# brmbora8.net
KiCad netlist of a schematic drawn in EAGLE
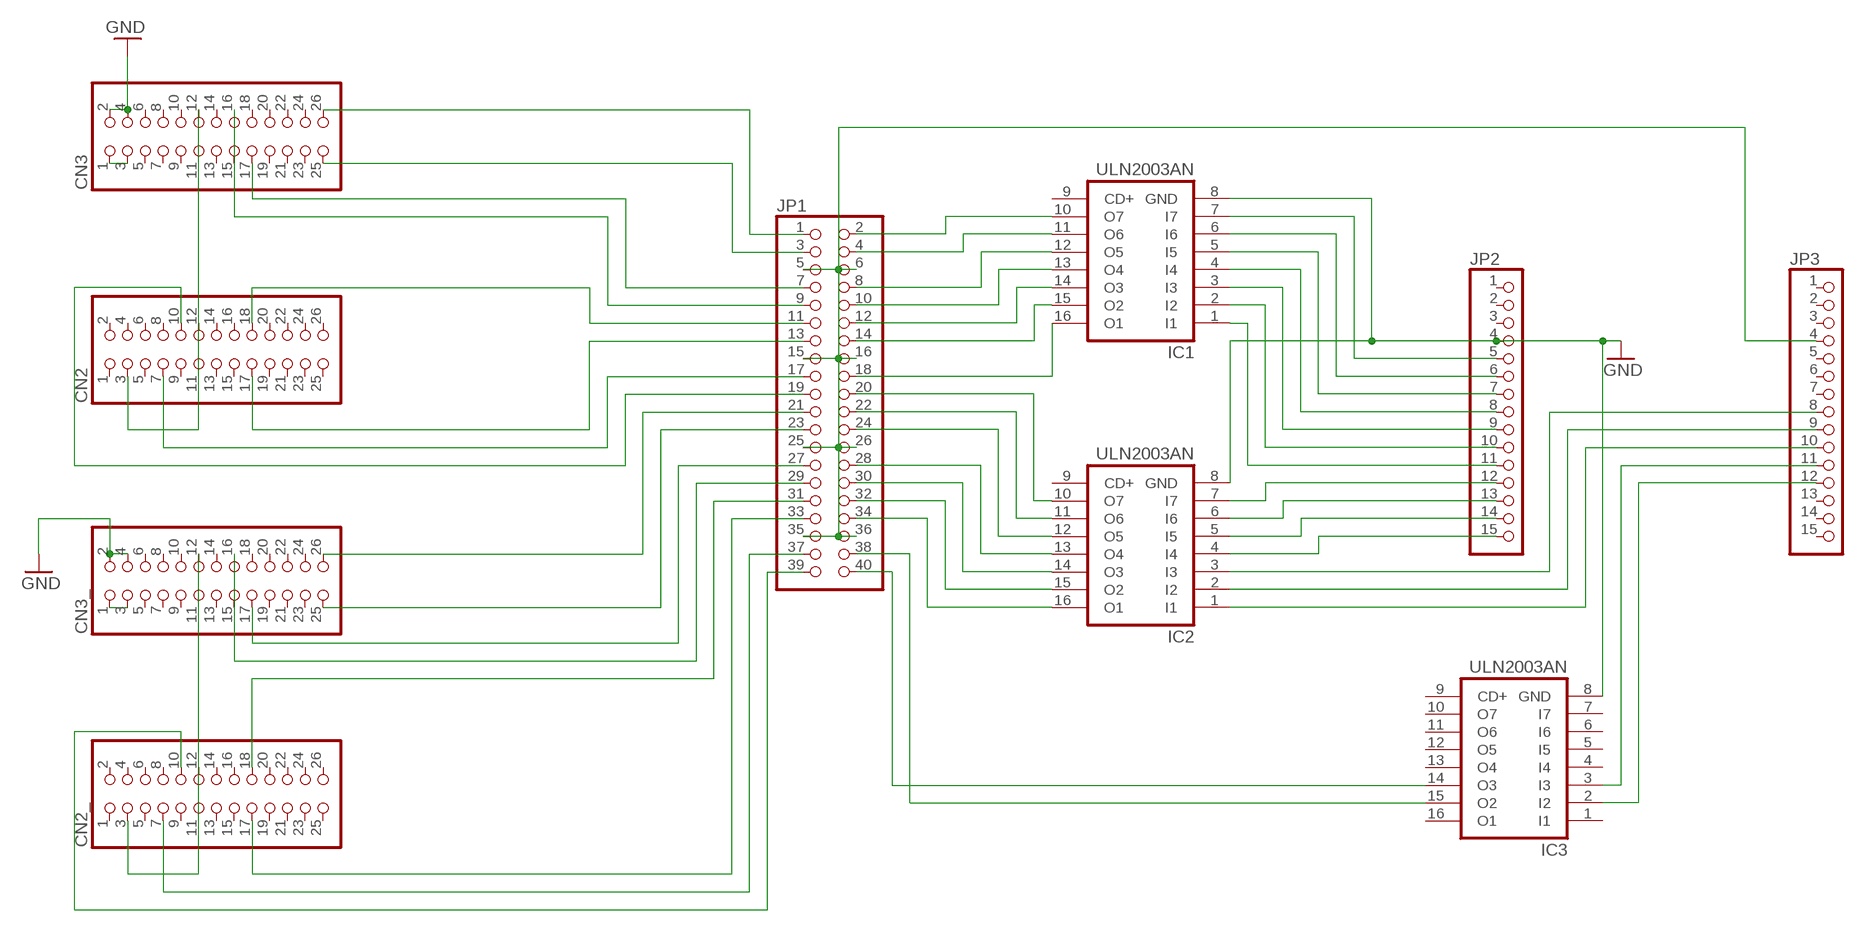
[diagram p0: schematic, sheet 1]

(export (version "E")
  (design (tool "Eeschema 10.0.6"))
  (components
    (comp (ref "CN2")
      (value "PINHD-2X13")
      (footprint "eagle-import:2X13")
      (libsource (lib "eagle-import") (part "PINHD-2X13"))
    )
    (comp (ref "CN2_")
      (value "PINHD-2X13")
      (footprint "eagle-import:2X13")
      (libsource (lib "eagle-import") (part "PINHD-2X13"))
    )
    (comp (ref "CN3")
      (value "PINHD-2X13")
      (footprint "eagle-import:2X13")
      (libsource (lib "eagle-import") (part "PINHD-2X13"))
    )
    (comp (ref "CN3_")
      (value "PINHD-2X13")
      (footprint "eagle-import:2X13")
      (libsource (lib "eagle-import") (part "PINHD-2X13"))
    )
    (comp (ref "IC1")
      (value "ULN2003AN")
      (footprint "eagle-import:DIL16")
      (libsource (lib "eagle-import") (part "ULN2003AN"))
    )
    (comp (ref "IC2")
      (value "ULN2003AN")
      (footprint "eagle-import:DIL16")
      (libsource (lib "eagle-import") (part "ULN2003AN"))
    )
    (comp (ref "IC3")
      (value "ULN2003AN")
      (footprint "eagle-import:DIL16")
      (libsource (lib "eagle-import") (part "ULN2003AN"))
    )
    (comp (ref "JP1")
      (value "PINHD-2X20-BIG")
      (footprint "eagle-import:2X20-BIG")
      (libsource (lib "eagle-import") (part "PINHD-2X20-BIG"))
    )
    (comp (ref "JP2")
      (value "PINHD-1X15")
      (footprint "eagle-import:1X15")
      (libsource (lib "eagle-import") (part "PINHD-1X15"))
    )
    (comp (ref "JP3")
      (value "PINHD-1X15")
      (footprint "eagle-import:1X15")
      (libsource (lib "eagle-import") (part "PINHD-1X15"))
    )
  )
  (nets
    (net (code "1") (name "GND") (class "Default")
      (node (ref "CN3") (pin "2") (pinfunction "2_2") (pintype "passive"))
      (node (ref "CN3") (pin "4") (pinfunction "4_4") (pintype "passive"))
      (node (ref "CN3_") (pin "2") (pinfunction "2_2") (pintype "passive"))
      (node (ref "CN3_") (pin "4") (pinfunction "4_4") (pintype "passive"))
      (node (ref "IC1") (pin "8") (pinfunction "GND_8") (pintype "power_in"))
      (node (ref "IC2") (pin "8") (pinfunction "GND_8") (pintype "power_in"))
      (node (ref "IC3") (pin "8") (pinfunction "GND_8") (pintype "power_in"))
      (node (ref "JP2") (pin "4") (pinfunction "4_4") (pintype "passive"))
    )
    (net (code "2") (name "Net-(CN2-Pad7)") (class "Default")
      (node (ref "CN2") (pin "7") (pinfunction "7_7") (pintype "passive"))
      (node (ref "JP1") (pin "17") (pinfunction "17_17") (pintype "passive"))
    )
    (net (code "3") (name "Net-(CN2-Pad10)") (class "Default")
      (node (ref "CN2") (pin "10") (pinfunction "10_10") (pintype "passive"))
      (node (ref "JP1") (pin "19") (pinfunction "19_19") (pintype "passive"))
    )
    (net (code "4") (name "Net-(CN2-Pad11)") (class "Default")
      (node (ref "CN2") (pin "11") (pinfunction "11_11") (pintype "passive"))
      (node (ref "CN2") (pin "3") (pinfunction "3_3") (pintype "passive"))
      (node (ref "CN3") (pin "12") (pinfunction "12_12") (pintype "passive"))
    )
    (net (code "5") (name "Net-(CN2-Pad17)") (class "Default")
      (node (ref "CN2") (pin "17") (pinfunction "17_17") (pintype "passive"))
      (node (ref "JP1") (pin "13") (pinfunction "13_13") (pintype "passive"))
    )
    (net (code "6") (name "Net-(CN2-Pad18)") (class "Default")
      (node (ref "CN2") (pin "18") (pinfunction "18_18") (pintype "passive"))
      (node (ref "JP1") (pin "11") (pinfunction "11_11") (pintype "passive"))
    )
    (net (code "7") (name "Net-(CN2_-Pad7)") (class "Default")
      (node (ref "CN2_") (pin "7") (pinfunction "7_7") (pintype "passive"))
      (node (ref "JP1") (pin "37") (pinfunction "37_37") (pintype "passive"))
    )
    (net (code "8") (name "Net-(CN2_-Pad10)") (class "Default")
      (node (ref "CN2_") (pin "10") (pinfunction "10_10") (pintype "passive"))
      (node (ref "JP1") (pin "39") (pinfunction "39_39") (pintype "passive"))
    )
    (net (code "9") (name "Net-(CN2_-Pad11)") (class "Default")
      (node (ref "CN2_") (pin "11") (pinfunction "11_11") (pintype "passive"))
      (node (ref "CN2_") (pin "3") (pinfunction "3_3") (pintype "passive"))
      (node (ref "CN3_") (pin "12") (pinfunction "12_12") (pintype "passive"))
    )
    (net (code "10") (name "Net-(CN2_-Pad17)") (class "Default")
      (node (ref "CN2_") (pin "17") (pinfunction "17_17") (pintype "passive"))
      (node (ref "JP1") (pin "33") (pinfunction "33_33") (pintype "passive"))
    )
    (net (code "11") (name "Net-(CN2_-Pad18)") (class "Default")
      (node (ref "CN2_") (pin "18") (pinfunction "18_18") (pintype "passive"))
      (node (ref "JP1") (pin "31") (pinfunction "31_31") (pintype "passive"))
    )
    (net (code "12") (name "Net-(CN3-Pad1)") (class "Default")
      (node (ref "CN3") (pin "1") (pinfunction "1_1") (pintype "passive"))
      (node (ref "CN3") (pin "3") (pinfunction "3_3") (pintype "passive"))
    )
    (net (code "13") (name "Net-(CN3-Pad16)") (class "Default")
      (node (ref "CN3") (pin "16") (pinfunction "16_16") (pintype "passive"))
      (node (ref "JP1") (pin "9") (pinfunction "9_9") (pintype "passive"))
    )
    (net (code "14") (name "Net-(CN3-Pad17)") (class "Default")
      (node (ref "CN3") (pin "17") (pinfunction "17_17") (pintype "passive"))
      (node (ref "JP1") (pin "7") (pinfunction "7_7") (pintype "passive"))
    )
    (net (code "15") (name "Net-(CN3-Pad25)") (class "Default")
      (node (ref "CN3") (pin "25") (pinfunction "25_25") (pintype "passive"))
      (node (ref "JP1") (pin "3") (pinfunction "3_3") (pintype "passive"))
    )
    (net (code "16") (name "Net-(CN3-Pad26)") (class "Default")
      (node (ref "CN3") (pin "26") (pinfunction "26_26") (pintype "passive"))
      (node (ref "JP1") (pin "1") (pinfunction "1_1") (pintype "passive"))
    )
    (net (code "17") (name "Net-(CN3_-Pad1)") (class "Default")
      (node (ref "CN3_") (pin "1") (pinfunction "1_1") (pintype "passive"))
      (node (ref "CN3_") (pin "3") (pinfunction "3_3") (pintype "passive"))
    )
    (net (code "18") (name "Net-(CN3_-Pad16)") (class "Default")
      (node (ref "CN3_") (pin "16") (pinfunction "16_16") (pintype "passive"))
      (node (ref "JP1") (pin "29") (pinfunction "29_29") (pintype "passive"))
    )
    (net (code "19") (name "Net-(CN3_-Pad17)") (class "Default")
      (node (ref "CN3_") (pin "17") (pinfunction "17_17") (pintype "passive"))
      (node (ref "JP1") (pin "27") (pinfunction "27_27") (pintype "passive"))
    )
    (net (code "20") (name "Net-(CN3_-Pad25)") (class "Default")
      (node (ref "CN3_") (pin "25") (pinfunction "25_25") (pintype "passive"))
      (node (ref "JP1") (pin "23") (pinfunction "23_23") (pintype "passive"))
    )
    (net (code "21") (name "Net-(CN3_-Pad26)") (class "Default")
      (node (ref "CN3_") (pin "26") (pinfunction "26_26") (pintype "passive"))
      (node (ref "JP1") (pin "21") (pinfunction "21_21") (pintype "passive"))
    )
    (net (code "22") (name "Net-(IC1-I1)") (class "Default")
      (node (ref "IC1") (pin "1") (pinfunction "I1_1") (pintype "input"))
      (node (ref "JP2") (pin "11") (pinfunction "11_11") (pintype "passive"))
    )
    (net (code "23") (name "Net-(IC1-I2)") (class "Default")
      (node (ref "IC1") (pin "2") (pinfunction "I2_2") (pintype "input"))
      (node (ref "JP2") (pin "10") (pinfunction "10_10") (pintype "passive"))
    )
    (net (code "24") (name "Net-(IC1-I3)") (class "Default")
      (node (ref "IC1") (pin "3") (pinfunction "I3_3") (pintype "input"))
      (node (ref "JP2") (pin "9") (pinfunction "9_9") (pintype "passive"))
    )
    (net (code "25") (name "Net-(IC1-I4)") (class "Default")
      (node (ref "IC1") (pin "4") (pinfunction "I4_4") (pintype "input"))
      (node (ref "JP2") (pin "8") (pinfunction "8_8") (pintype "passive"))
    )
    (net (code "26") (name "Net-(IC1-I5)") (class "Default")
      (node (ref "IC1") (pin "5") (pinfunction "I5_5") (pintype "input"))
      (node (ref "JP2") (pin "7") (pinfunction "7_7") (pintype "passive"))
    )
    (net (code "27") (name "Net-(IC1-I6)") (class "Default")
      (node (ref "IC1") (pin "6") (pinfunction "I6_6") (pintype "input"))
      (node (ref "JP2") (pin "6") (pinfunction "6_6") (pintype "passive"))
    )
    (net (code "28") (name "Net-(IC1-I7)") (class "Default")
      (node (ref "IC1") (pin "7") (pinfunction "I7_7") (pintype "input"))
      (node (ref "JP2") (pin "5") (pinfunction "5_5") (pintype "passive"))
    )
    (net (code "29") (name "Net-(IC1-O1)") (class "Default")
      (node (ref "IC1") (pin "16") (pinfunction "O1_16") (pintype "open_collector"))
      (node (ref "JP1") (pin "18") (pinfunction "18_18") (pintype "passive"))
    )
    (net (code "30") (name "Net-(IC1-O2)") (class "Default")
      (node (ref "IC1") (pin "15") (pinfunction "O2_15") (pintype "open_collector"))
      (node (ref "JP1") (pin "14") (pinfunction "14_14") (pintype "passive"))
    )
    (net (code "31") (name "Net-(IC1-O3)") (class "Default")
      (node (ref "IC1") (pin "14") (pinfunction "O3_14") (pintype "open_collector"))
      (node (ref "JP1") (pin "12") (pinfunction "12_12") (pintype "passive"))
    )
    (net (code "32") (name "Net-(IC1-O4)") (class "Default")
      (node (ref "IC1") (pin "13") (pinfunction "O4_13") (pintype "open_collector"))
      (node (ref "JP1") (pin "10") (pinfunction "10_10") (pintype "passive"))
    )
    (net (code "33") (name "Net-(IC1-O5)") (class "Default")
      (node (ref "IC1") (pin "12") (pinfunction "O5_12") (pintype "open_collector"))
      (node (ref "JP1") (pin "8") (pinfunction "8_8") (pintype "passive"))
    )
    (net (code "34") (name "Net-(IC1-O6)") (class "Default")
      (node (ref "IC1") (pin "11") (pinfunction "O6_11") (pintype "open_collector"))
      (node (ref "JP1") (pin "4") (pinfunction "4_4") (pintype "passive"))
    )
    (net (code "35") (name "Net-(IC1-O7)") (class "Default")
      (node (ref "IC1") (pin "10") (pinfunction "O7_10") (pintype "open_collector"))
      (node (ref "JP1") (pin "2") (pinfunction "2_2") (pintype "passive"))
    )
    (net (code "36") (name "Net-(IC2-I1)") (class "Default")
      (node (ref "IC2") (pin "1") (pinfunction "I1_1") (pintype "input"))
      (node (ref "JP3") (pin "10") (pinfunction "10_10") (pintype "passive"))
    )
    (net (code "37") (name "Net-(IC2-I2)") (class "Default")
      (node (ref "IC2") (pin "2") (pinfunction "I2_2") (pintype "input"))
      (node (ref "JP3") (pin "9") (pinfunction "9_9") (pintype "passive"))
    )
    (net (code "38") (name "Net-(IC2-I3)") (class "Default")
      (node (ref "IC2") (pin "3") (pinfunction "I3_3") (pintype "input"))
      (node (ref "JP3") (pin "8") (pinfunction "8_8") (pintype "passive"))
    )
    (net (code "39") (name "Net-(IC2-I4)") (class "Default")
      (node (ref "IC2") (pin "4") (pinfunction "I4_4") (pintype "input"))
      (node (ref "JP2") (pin "15") (pinfunction "15_15") (pintype "passive"))
    )
    (net (code "40") (name "Net-(IC2-I5)") (class "Default")
      (node (ref "IC2") (pin "5") (pinfunction "I5_5") (pintype "input"))
      (node (ref "JP2") (pin "14") (pinfunction "14_14") (pintype "passive"))
    )
    (net (code "41") (name "Net-(IC2-I6)") (class "Default")
      (node (ref "IC2") (pin "6") (pinfunction "I6_6") (pintype "input"))
      (node (ref "JP2") (pin "13") (pinfunction "13_13") (pintype "passive"))
    )
    (net (code "42") (name "Net-(IC2-I7)") (class "Default")
      (node (ref "IC2") (pin "7") (pinfunction "I7_7") (pintype "input"))
      (node (ref "JP2") (pin "12") (pinfunction "12_12") (pintype "passive"))
    )
    (net (code "43") (name "Net-(IC2-O1)") (class "Default")
      (node (ref "IC2") (pin "16") (pinfunction "O1_16") (pintype "open_collector"))
      (node (ref "JP1") (pin "34") (pinfunction "34_34") (pintype "passive"))
    )
    (net (code "44") (name "Net-(IC2-O2)") (class "Default")
      (node (ref "IC2") (pin "15") (pinfunction "O2_15") (pintype "open_collector"))
      (node (ref "JP1") (pin "32") (pinfunction "32_32") (pintype "passive"))
    )
    (net (code "45") (name "Net-(IC2-O3)") (class "Default")
      (node (ref "IC2") (pin "14") (pinfunction "O3_14") (pintype "open_collector"))
      (node (ref "JP1") (pin "30") (pinfunction "30_30") (pintype "passive"))
    )
    (net (code "46") (name "Net-(IC2-O4)") (class "Default")
      (node (ref "IC2") (pin "13") (pinfunction "O4_13") (pintype "open_collector"))
      (node (ref "JP1") (pin "28") (pinfunction "28_28") (pintype "passive"))
    )
    (net (code "47") (name "Net-(IC2-O5)") (class "Default")
      (node (ref "IC2") (pin "12") (pinfunction "O5_12") (pintype "open_collector"))
      (node (ref "JP1") (pin "24") (pinfunction "24_24") (pintype "passive"))
    )
    (net (code "48") (name "Net-(IC2-O6)") (class "Default")
      (node (ref "IC2") (pin "11") (pinfunction "O6_11") (pintype "open_collector"))
      (node (ref "JP1") (pin "22") (pinfunction "22_22") (pintype "passive"))
    )
    (net (code "49") (name "Net-(IC2-O7)") (class "Default")
      (node (ref "IC2") (pin "10") (pinfunction "O7_10") (pintype "open_collector"))
      (node (ref "JP1") (pin "20") (pinfunction "20_20") (pintype "passive"))
    )
    (net (code "50") (name "Net-(IC3-I2)") (class "Default")
      (node (ref "IC3") (pin "2") (pinfunction "I2_2") (pintype "input"))
      (node (ref "JP3") (pin "12") (pinfunction "12_12") (pintype "passive"))
    )
    (net (code "51") (name "Net-(IC3-I3)") (class "Default")
      (node (ref "IC3") (pin "3") (pinfunction "I3_3") (pintype "input"))
      (node (ref "JP3") (pin "11") (pinfunction "11_11") (pintype "passive"))
    )
    (net (code "52") (name "Net-(IC3-O2)") (class "Default")
      (node (ref "IC3") (pin "15") (pinfunction "O2_15") (pintype "open_collector"))
      (node (ref "JP1") (pin "38") (pinfunction "38_38") (pintype "passive"))
    )
    (net (code "53") (name "Net-(IC3-O3)") (class "Default")
      (node (ref "IC3") (pin "14") (pinfunction "O3_14") (pintype "open_collector"))
      (node (ref "JP1") (pin "40") (pinfunction "40_40") (pintype "passive"))
    )
    (net (code "54") (name "Net-(JP1-Pad15)") (class "Default")
      (node (ref "JP1") (pin "15") (pinfunction "15_15") (pintype "passive"))
      (node (ref "JP1") (pin "16") (pinfunction "16_16") (pintype "passive"))
      (node (ref "JP1") (pin "25") (pinfunction "25_25") (pintype "passive"))
      (node (ref "JP1") (pin "26") (pinfunction "26_26") (pintype "passive"))
      (node (ref "JP1") (pin "35") (pinfunction "35_35") (pintype "passive"))
      (node (ref "JP1") (pin "36") (pinfunction "36_36") (pintype "passive"))
      (node (ref "JP1") (pin "5") (pinfunction "5_5") (pintype "passive"))
      (node (ref "JP1") (pin "6") (pinfunction "6_6") (pintype "passive"))
      (node (ref "JP3") (pin "4") (pinfunction "4_4") (pintype "passive"))
    )
    (net (code "55") (name "unconnected-(CN2-Pad1)") (class "Default")
      (node (ref "CN2") (pin "1") (pinfunction "1_1") (pintype "passive"))
    )
    (net (code "56") (name "unconnected-(CN2-Pad2)") (class "Default")
      (node (ref "CN2") (pin "2") (pinfunction "2_2") (pintype "passive"))
    )
    (net (code "57") (name "unconnected-(CN2-Pad4)") (class "Default")
      (node (ref "CN2") (pin "4") (pinfunction "4_4") (pintype "passive"))
    )
    (net (code "58") (name "unconnected-(CN2-Pad5)") (class "Default")
      (node (ref "CN2") (pin "5") (pinfunction "5_5") (pintype "passive"))
    )
    (net (code "59") (name "unconnected-(CN2-Pad6)") (class "Default")
      (node (ref "CN2") (pin "6") (pinfunction "6_6") (pintype "passive"))
    )
    (net (code "60") (name "unconnected-(CN2-Pad8)") (class "Default")
      (node (ref "CN2") (pin "8") (pinfunction "8_8") (pintype "passive"))
    )
    (net (code "61") (name "unconnected-(CN2-Pad9)") (class "Default")
      (node (ref "CN2") (pin "9") (pinfunction "9_9") (pintype "passive"))
    )
    (net (code "62") (name "unconnected-(CN2-Pad12)") (class "Default")
      (node (ref "CN2") (pin "12") (pinfunction "12_12") (pintype "passive"))
    )
    (net (code "63") (name "unconnected-(CN2-Pad13)") (class "Default")
      (node (ref "CN2") (pin "13") (pinfunction "13_13") (pintype "passive"))
    )
    (net (code "64") (name "unconnected-(CN2-Pad14)") (class "Default")
      (node (ref "CN2") (pin "14") (pinfunction "14_14") (pintype "passive"))
    )
    (net (code "65") (name "unconnected-(CN2-Pad15)") (class "Default")
      (node (ref "CN2") (pin "15") (pinfunction "15_15") (pintype "passive"))
    )
    (net (code "66") (name "unconnected-(CN2-Pad16)") (class "Default")
      (node (ref "CN2") (pin "16") (pinfunction "16_16") (pintype "passive"))
    )
    (net (code "67") (name "unconnected-(CN2-Pad19)") (class "Default")
      (node (ref "CN2") (pin "19") (pinfunction "19_19") (pintype "passive"))
    )
    (net (code "68") (name "unconnected-(CN2-Pad20)") (class "Default")
      (node (ref "CN2") (pin "20") (pinfunction "20_20") (pintype "passive"))
    )
    (net (code "69") (name "unconnected-(CN2-Pad21)") (class "Default")
      (node (ref "CN2") (pin "21") (pinfunction "21_21") (pintype "passive"))
    )
    (net (code "70") (name "unconnected-(CN2-Pad22)") (class "Default")
      (node (ref "CN2") (pin "22") (pinfunction "22_22") (pintype "passive"))
    )
    (net (code "71") (name "unconnected-(CN2-Pad23)") (class "Default")
      (node (ref "CN2") (pin "23") (pinfunction "23_23") (pintype "passive"))
    )
    (net (code "72") (name "unconnected-(CN2-Pad24)") (class "Default")
      (node (ref "CN2") (pin "24") (pinfunction "24_24") (pintype "passive"))
    )
    (net (code "73") (name "unconnected-(CN2-Pad25)") (class "Default")
      (node (ref "CN2") (pin "25") (pinfunction "25_25") (pintype "passive"))
    )
    (net (code "74") (name "unconnected-(CN2-Pad26)") (class "Default")
      (node (ref "CN2") (pin "26") (pinfunction "26_26") (pintype "passive"))
    )
    (net (code "75") (name "unconnected-(CN2_-Pad1)") (class "Default")
      (node (ref "CN2_") (pin "1") (pinfunction "1_1") (pintype "passive"))
    )
    (net (code "76") (name "unconnected-(CN2_-Pad2)") (class "Default")
      (node (ref "CN2_") (pin "2") (pinfunction "2_2") (pintype "passive"))
    )
    (net (code "77") (name "unconnected-(CN2_-Pad4)") (class "Default")
      (node (ref "CN2_") (pin "4") (pinfunction "4_4") (pintype "passive"))
    )
    (net (code "78") (name "unconnected-(CN2_-Pad5)") (class "Default")
      (node (ref "CN2_") (pin "5") (pinfunction "5_5") (pintype "passive"))
    )
    (net (code "79") (name "unconnected-(CN2_-Pad6)") (class "Default")
      (node (ref "CN2_") (pin "6") (pinfunction "6_6") (pintype "passive"))
    )
    (net (code "80") (name "unconnected-(CN2_-Pad8)") (class "Default")
      (node (ref "CN2_") (pin "8") (pinfunction "8_8") (pintype "passive"))
    )
    (net (code "81") (name "unconnected-(CN2_-Pad9)") (class "Default")
      (node (ref "CN2_") (pin "9") (pinfunction "9_9") (pintype "passive"))
    )
    (net (code "82") (name "unconnected-(CN2_-Pad12)") (class "Default")
      (node (ref "CN2_") (pin "12") (pinfunction "12_12") (pintype "passive"))
    )
    (net (code "83") (name "unconnected-(CN2_-Pad13)") (class "Default")
      (node (ref "CN2_") (pin "13") (pinfunction "13_13") (pintype "passive"))
    )
    (net (code "84") (name "unconnected-(CN2_-Pad14)") (class "Default")
      (node (ref "CN2_") (pin "14") (pinfunction "14_14") (pintype "passive"))
    )
    (net (code "85") (name "unconnected-(CN2_-Pad15)") (class "Default")
      (node (ref "CN2_") (pin "15") (pinfunction "15_15") (pintype "passive"))
    )
    (net (code "86") (name "unconnected-(CN2_-Pad16)") (class "Default")
      (node (ref "CN2_") (pin "16") (pinfunction "16_16") (pintype "passive"))
    )
    (net (code "87") (name "unconnected-(CN2_-Pad19)") (class "Default")
      (node (ref "CN2_") (pin "19") (pinfunction "19_19") (pintype "passive"))
    )
    (net (code "88") (name "unconnected-(CN2_-Pad20)") (class "Default")
      (node (ref "CN2_") (pin "20") (pinfunction "20_20") (pintype "passive"))
    )
    (net (code "89") (name "unconnected-(CN2_-Pad21)") (class "Default")
      (node (ref "CN2_") (pin "21") (pinfunction "21_21") (pintype "passive"))
    )
    (net (code "90") (name "unconnected-(CN2_-Pad22)") (class "Default")
      (node (ref "CN2_") (pin "22") (pinfunction "22_22") (pintype "passive"))
    )
    (net (code "91") (name "unconnected-(CN2_-Pad23)") (class "Default")
      (node (ref "CN2_") (pin "23") (pinfunction "23_23") (pintype "passive"))
    )
    (net (code "92") (name "unconnected-(CN2_-Pad24)") (class "Default")
      (node (ref "CN2_") (pin "24") (pinfunction "24_24") (pintype "passive"))
    )
    (net (code "93") (name "unconnected-(CN2_-Pad25)") (class "Default")
      (node (ref "CN2_") (pin "25") (pinfunction "25_25") (pintype "passive"))
    )
    (net (code "94") (name "unconnected-(CN2_-Pad26)") (class "Default")
      (node (ref "CN2_") (pin "26") (pinfunction "26_26") (pintype "passive"))
    )
    (net (code "95") (name "unconnected-(CN3-Pad5)") (class "Default")
      (node (ref "CN3") (pin "5") (pinfunction "5_5") (pintype "passive"))
    )
    (net (code "96") (name "unconnected-(CN3-Pad6)") (class "Default")
      (node (ref "CN3") (pin "6") (pinfunction "6_6") (pintype "passive"))
    )
    (net (code "97") (name "unconnected-(CN3-Pad7)") (class "Default")
      (node (ref "CN3") (pin "7") (pinfunction "7_7") (pintype "passive"))
    )
    (net (code "98") (name "unconnected-(CN3-Pad8)") (class "Default")
      (node (ref "CN3") (pin "8") (pinfunction "8_8") (pintype "passive"))
    )
    (net (code "99") (name "unconnected-(CN3-Pad9)") (class "Default")
      (node (ref "CN3") (pin "9") (pinfunction "9_9") (pintype "passive"))
    )
    (net (code "100") (name "unconnected-(CN3-Pad10)") (class "Default")
      (node (ref "CN3") (pin "10") (pinfunction "10_10") (pintype "passive"))
    )
    (net (code "101") (name "unconnected-(CN3-Pad11)") (class "Default")
      (node (ref "CN3") (pin "11") (pinfunction "11_11") (pintype "passive"))
    )
    (net (code "102") (name "unconnected-(CN3-Pad13)") (class "Default")
      (node (ref "CN3") (pin "13") (pinfunction "13_13") (pintype "passive"))
    )
    (net (code "103") (name "unconnected-(CN3-Pad14)") (class "Default")
      (node (ref "CN3") (pin "14") (pinfunction "14_14") (pintype "passive"))
    )
    (net (code "104") (name "unconnected-(CN3-Pad15)") (class "Default")
      (node (ref "CN3") (pin "15") (pinfunction "15_15") (pintype "passive"))
    )
    (net (code "105") (name "unconnected-(CN3-Pad18)") (class "Default")
      (node (ref "CN3") (pin "18") (pinfunction "18_18") (pintype "passive"))
    )
    (net (code "106") (name "unconnected-(CN3-Pad19)") (class "Default")
      (node (ref "CN3") (pin "19") (pinfunction "19_19") (pintype "passive"))
    )
    (net (code "107") (name "unconnected-(CN3-Pad20)") (class "Default")
      (node (ref "CN3") (pin "20") (pinfunction "20_20") (pintype "passive"))
    )
    (net (code "108") (name "unconnected-(CN3-Pad21)") (class "Default")
      (node (ref "CN3") (pin "21") (pinfunction "21_21") (pintype "passive"))
    )
    (net (code "109") (name "unconnected-(CN3-Pad22)") (class "Default")
      (node (ref "CN3") (pin "22") (pinfunction "22_22") (pintype "passive"))
    )
    (net (code "110") (name "unconnected-(CN3-Pad23)") (class "Default")
      (node (ref "CN3") (pin "23") (pinfunction "23_23") (pintype "passive"))
    )
    (net (code "111") (name "unconnected-(CN3-Pad24)") (class "Default")
      (node (ref "CN3") (pin "24") (pinfunction "24_24") (pintype "passive"))
    )
    (net (code "112") (name "unconnected-(CN3_-Pad5)") (class "Default")
      (node (ref "CN3_") (pin "5") (pinfunction "5_5") (pintype "passive"))
    )
    (net (code "113") (name "unconnected-(CN3_-Pad6)") (class "Default")
      (node (ref "CN3_") (pin "6") (pinfunction "6_6") (pintype "passive"))
    )
    (net (code "114") (name "unconnected-(CN3_-Pad7)") (class "Default")
      (node (ref "CN3_") (pin "7") (pinfunction "7_7") (pintype "passive"))
    )
    (net (code "115") (name "unconnected-(CN3_-Pad8)") (class "Default")
      (node (ref "CN3_") (pin "8") (pinfunction "8_8") (pintype "passive"))
    )
    (net (code "116") (name "unconnected-(CN3_-Pad9)") (class "Default")
      (node (ref "CN3_") (pin "9") (pinfunction "9_9") (pintype "passive"))
    )
    (net (code "117") (name "unconnected-(CN3_-Pad10)") (class "Default")
      (node (ref "CN3_") (pin "10") (pinfunction "10_10") (pintype "passive"))
    )
    (net (code "118") (name "unconnected-(CN3_-Pad11)") (class "Default")
      (node (ref "CN3_") (pin "11") (pinfunction "11_11") (pintype "passive"))
    )
    (net (code "119") (name "unconnected-(CN3_-Pad13)") (class "Default")
      (node (ref "CN3_") (pin "13") (pinfunction "13_13") (pintype "passive"))
    )
    (net (code "120") (name "unconnected-(CN3_-Pad14)") (class "Default")
      (node (ref "CN3_") (pin "14") (pinfunction "14_14") (pintype "passive"))
    )
    (net (code "121") (name "unconnected-(CN3_-Pad15)") (class "Default")
      (node (ref "CN3_") (pin "15") (pinfunction "15_15") (pintype "passive"))
    )
    (net (code "122") (name "unconnected-(CN3_-Pad18)") (class "Default")
      (node (ref "CN3_") (pin "18") (pinfunction "18_18") (pintype "passive"))
    )
    (net (code "123") (name "unconnected-(CN3_-Pad19)") (class "Default")
      (node (ref "CN3_") (pin "19") (pinfunction "19_19") (pintype "passive"))
    )
    (net (code "124") (name "unconnected-(CN3_-Pad20)") (class "Default")
      (node (ref "CN3_") (pin "20") (pinfunction "20_20") (pintype "passive"))
    )
    (net (code "125") (name "unconnected-(CN3_-Pad21)") (class "Default")
      (node (ref "CN3_") (pin "21") (pinfunction "21_21") (pintype "passive"))
    )
    (net (code "126") (name "unconnected-(CN3_-Pad22)") (class "Default")
      (node (ref "CN3_") (pin "22") (pinfunction "22_22") (pintype "passive"))
    )
    (net (code "127") (name "unconnected-(CN3_-Pad23)") (class "Default")
      (node (ref "CN3_") (pin "23") (pinfunction "23_23") (pintype "passive"))
    )
    (net (code "128") (name "unconnected-(CN3_-Pad24)") (class "Default")
      (node (ref "CN3_") (pin "24") (pinfunction "24_24") (pintype "passive"))
    )
    (net (code "129") (name "unconnected-(IC1-CD+-Pad9)") (class "Default")
      (node (ref "IC1") (pin "9") (pinfunction "CD+_9") (pintype "passive"))
    )
    (net (code "130") (name "unconnected-(IC2-CD+-Pad9)") (class "Default")
      (node (ref "IC2") (pin "9") (pinfunction "CD+_9") (pintype "passive"))
    )
    (net (code "131") (name "unconnected-(IC3-CD+-Pad9)") (class "Default")
      (node (ref "IC3") (pin "9") (pinfunction "CD+_9") (pintype "passive"))
    )
    (net (code "132") (name "unconnected-(IC3-I1-Pad1)") (class "Default")
      (node (ref "IC3") (pin "1") (pinfunction "I1_1") (pintype "input"))
    )
    (net (code "133") (name "unconnected-(IC3-I4-Pad4)") (class "Default")
      (node (ref "IC3") (pin "4") (pinfunction "I4_4") (pintype "input"))
    )
    (net (code "134") (name "unconnected-(IC3-I5-Pad5)") (class "Default")
      (node (ref "IC3") (pin "5") (pinfunction "I5_5") (pintype "input"))
    )
    (net (code "135") (name "unconnected-(IC3-I6-Pad6)") (class "Default")
      (node (ref "IC3") (pin "6") (pinfunction "I6_6") (pintype "input"))
    )
    (net (code "136") (name "unconnected-(IC3-I7-Pad7)") (class "Default")
      (node (ref "IC3") (pin "7") (pinfunction "I7_7") (pintype "input"))
    )
    (net (code "137") (name "unconnected-(IC3-O1-Pad16)") (class "Default")
      (node (ref "IC3") (pin "16") (pinfunction "O1_16") (pintype "open_collector"))
    )
    (net (code "138") (name "unconnected-(IC3-O4-Pad13)") (class "Default")
      (node (ref "IC3") (pin "13") (pinfunction "O4_13") (pintype "open_collector"))
    )
    (net (code "139") (name "unconnected-(IC3-O5-Pad12)") (class "Default")
      (node (ref "IC3") (pin "12") (pinfunction "O5_12") (pintype "open_collector"))
    )
    (net (code "140") (name "unconnected-(IC3-O6-Pad11)") (class "Default")
      (node (ref "IC3") (pin "11") (pinfunction "O6_11") (pintype "open_collector"))
    )
    (net (code "141") (name "unconnected-(IC3-O7-Pad10)") (class "Default")
      (node (ref "IC3") (pin "10") (pinfunction "O7_10") (pintype "open_collector"))
    )
    (net (code "142") (name "unconnected-(JP2-Pad1)") (class "Default")
      (node (ref "JP2") (pin "1") (pinfunction "1_1") (pintype "passive"))
    )
    (net (code "143") (name "unconnected-(JP2-Pad2)") (class "Default")
      (node (ref "JP2") (pin "2") (pinfunction "2_2") (pintype "passive"))
    )
    (net (code "144") (name "unconnected-(JP2-Pad3)") (class "Default")
      (node (ref "JP2") (pin "3") (pinfunction "3_3") (pintype "passive"))
    )
    (net (code "145") (name "unconnected-(JP3-Pad1)") (class "Default")
      (node (ref "JP3") (pin "1") (pinfunction "1_1") (pintype "passive"))
    )
    (net (code "146") (name "unconnected-(JP3-Pad2)") (class "Default")
      (node (ref "JP3") (pin "2") (pinfunction "2_2") (pintype "passive"))
    )
    (net (code "147") (name "unconnected-(JP3-Pad3)") (class "Default")
      (node (ref "JP3") (pin "3") (pinfunction "3_3") (pintype "passive"))
    )
    (net (code "148") (name "unconnected-(JP3-Pad5)") (class "Default")
      (node (ref "JP3") (pin "5") (pinfunction "5_5") (pintype "passive"))
    )
    (net (code "149") (name "unconnected-(JP3-Pad6)") (class "Default")
      (node (ref "JP3") (pin "6") (pinfunction "6_6") (pintype "passive"))
    )
    (net (code "150") (name "unconnected-(JP3-Pad7)") (class "Default")
      (node (ref "JP3") (pin "7") (pinfunction "7_7") (pintype "passive"))
    )
    (net (code "151") (name "unconnected-(JP3-Pad13)") (class "Default")
      (node (ref "JP3") (pin "13") (pinfunction "13_13") (pintype "passive"))
    )
    (net (code "152") (name "unconnected-(JP3-Pad14)") (class "Default")
      (node (ref "JP3") (pin "14") (pinfunction "14_14") (pintype "passive"))
    )
    (net (code "153") (name "unconnected-(JP3-Pad15)") (class "Default")
      (node (ref "JP3") (pin "15") (pinfunction "15_15") (pintype "passive"))
    )
  )
)
